# design.net
KiCad netlist of a schematic drawn in EAGLE
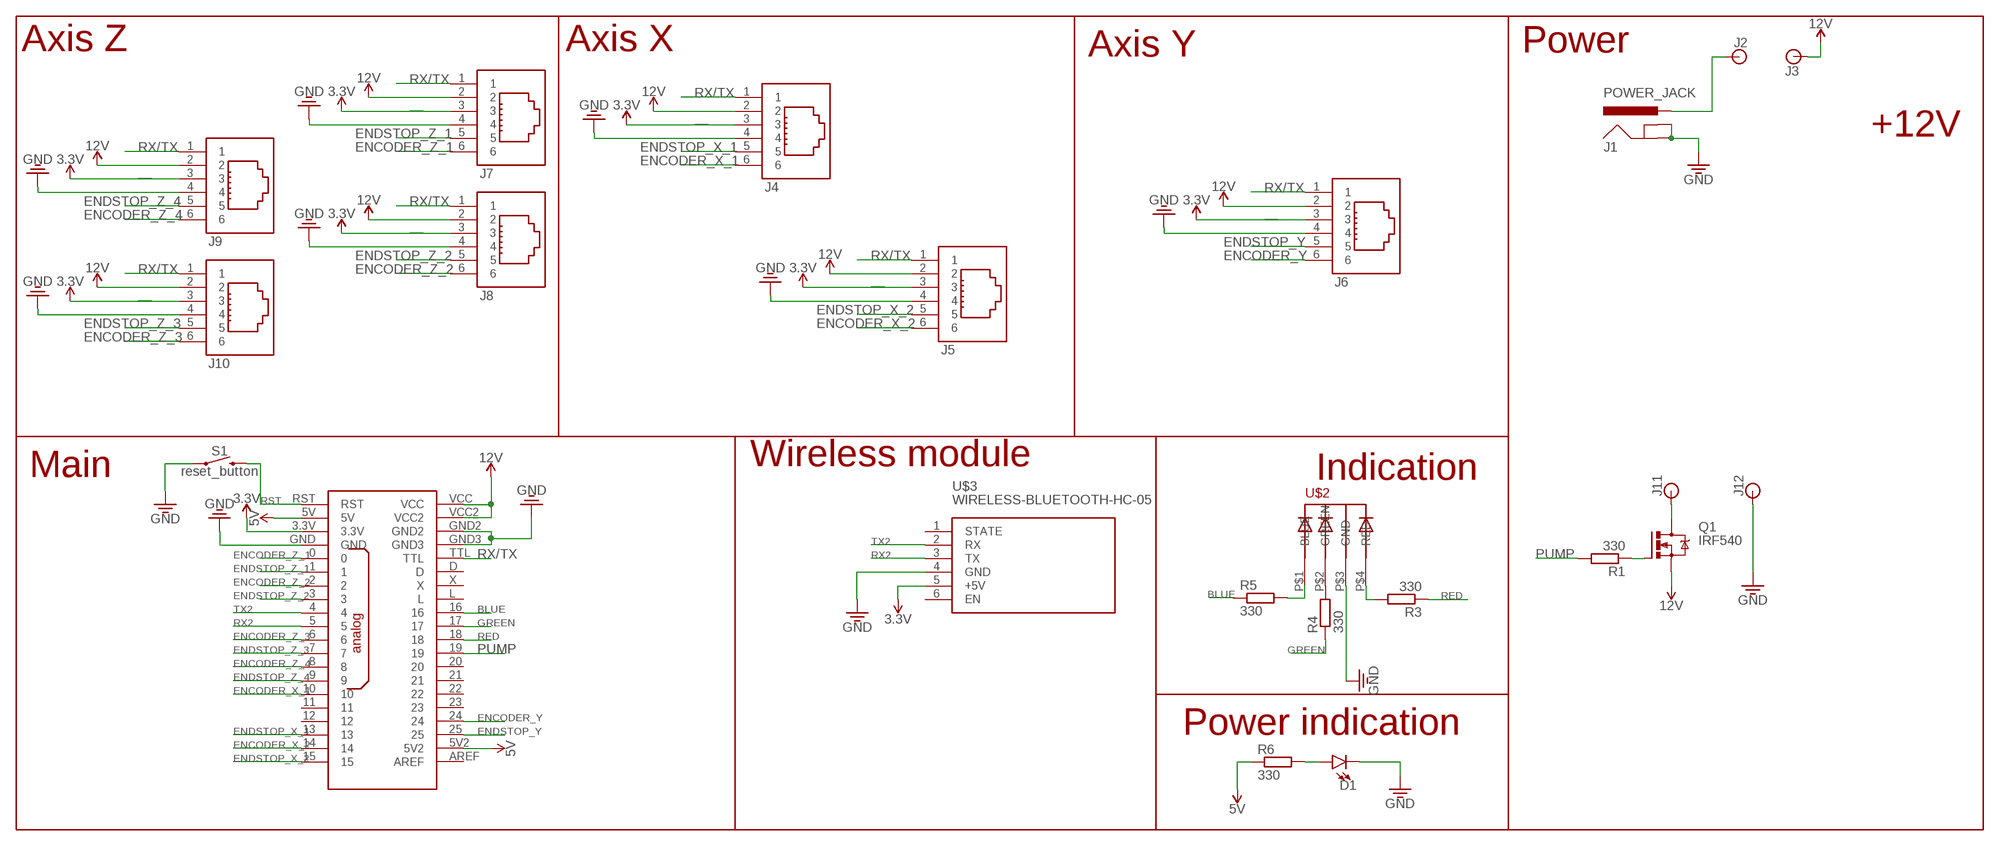
[diagram p0: schematic, sheet 1]

(export (version "E")
  (design (tool "Eeschema 10.0.6"))
  (components
    (comp (ref "D1")
      (value "LED5MM")
      (footprint "eagle-import:LED_5MM")
      (libsource (lib "eagle-import") (part "LED5MM"))
    )
    (comp (ref "J1")
      (value "POWER_JACK")
      (footprint "eagle-import:POWER_JACK_PTH")
      (libsource (lib "eagle-import") (part "POWER_JACK"))
    )
    (comp (ref "J2")
      (value "BANANA_CONN")
      (footprint "eagle-import:BANANA_CONN")
      (libsource (lib "eagle-import") (part "BANANA_CONN"))
    )
    (comp (ref "J3")
      (value "BANANA_CONN")
      (footprint "eagle-import:BANANA_CONN")
      (libsource (lib "eagle-import") (part "BANANA_CONN"))
    )
    (comp (ref "J4")
      (value "615006138421")
      (footprint "eagle-import:615006138421")
      (libsource (lib "eagle-import") (part "615006138421"))
    )
    (comp (ref "J5")
      (value "615006138421")
      (footprint "eagle-import:615006138421")
      (libsource (lib "eagle-import") (part "615006138421"))
    )
    (comp (ref "J6")
      (value "615006138421")
      (footprint "eagle-import:615006138421")
      (libsource (lib "eagle-import") (part "615006138421"))
    )
    (comp (ref "J7")
      (value "615006138421")
      (footprint "eagle-import:615006138421")
      (libsource (lib "eagle-import") (part "615006138421"))
    )
    (comp (ref "J8")
      (value "615006138421")
      (footprint "eagle-import:615006138421")
      (libsource (lib "eagle-import") (part "615006138421"))
    )
    (comp (ref "J9")
      (value "615006138421")
      (footprint "eagle-import:615006138421")
      (libsource (lib "eagle-import") (part "615006138421"))
    )
    (comp (ref "J10")
      (value "615006138421")
      (footprint "eagle-import:615006138421")
      (libsource (lib "eagle-import") (part "615006138421"))
    )
    (comp (ref "J11")
      (value "BANANA_CONN")
      (footprint "eagle-import:BANANA_CONN")
      (libsource (lib "eagle-import") (part "BANANA_CONN"))
    )
    (comp (ref "J12")
      (value "BANANA_CONN")
      (footprint "eagle-import:BANANA_CONN")
      (libsource (lib "eagle-import") (part "BANANA_CONN"))
    )
    (comp (ref "Q1")
      (value "IRF540")
      (footprint "eagle-import:TO220BV")
      (libsource (lib "eagle-import") (part "IRF540"))
    )
    (comp (ref "R1")
      (value "330")
      (footprint "eagle-import:0204_7")
      (libsource (lib "eagle-import") (part "R-EU_0204/7"))
    )
    (comp (ref "R3")
      (value "330")
      (footprint "eagle-import:0204_7")
      (libsource (lib "eagle-import") (part "R-EU_0204/7"))
    )
    (comp (ref "R4")
      (value "330")
      (footprint "eagle-import:0204_7")
      (libsource (lib "eagle-import") (part "R-EU_0204/7"))
    )
    (comp (ref "R5")
      (value "330")
      (footprint "eagle-import:0204_7")
      (libsource (lib "eagle-import") (part "R-EU_0204/7"))
    )
    (comp (ref "R6")
      (value "330")
      (footprint "eagle-import:0204_7")
      (libsource (lib "eagle-import") (part "R-EU_0204/7"))
    )
    (comp (ref "S1")
      (value "reset_button")
      (footprint "eagle-import:TACTILE_SWITCH_PTH_6.0MM")
      (libsource (lib "eagle-import") (part "MOMENTARY-SWITCH-SPST-PTH-6.0MM"))
    )
    (comp (ref "U$1")
      (value "OPENCM9.04")
      (footprint "eagle-import:OPENCM9.04")
      (libsource (lib "eagle-import") (part "OPENCM9.04"))
    )
    (comp (ref "U$2")
      (value "5MMRGBLED")
      (footprint "eagle-import:LED5MMRGB")
      (libsource (lib "eagle-import") (part "5MMRGBLED"))
    )
    (comp (ref "U$3")
      (value "WIRELESS-BLUETOOTH-HC-05")
      (footprint "eagle-import:WIRELESS-BLUETOOTH-HC-05")
      (libsource (lib "eagle-import") (part "WIRELESS-BLUETOOTH-HC-05"))
    )
  )
  (nets
    (net (code "1") (name "/BLUE") (class "Default")
      (node (ref "R5") (pin "1") (pinfunction "1_1") (pintype "passive"))
      (node (ref "U$1") (pin "16") (pinfunction "16_16") (pintype "bidirectional"))
    )
    (net (code "2") (name "/ENCODER_X_1") (class "Default")
      (node (ref "J4") (pin "6") (pinfunction "6_6") (pintype "passive"))
      (node (ref "U$1") (pin "10") (pinfunction "10_10") (pintype "bidirectional"))
    )
    (net (code "3") (name "/ENCODER_X_2") (class "Default")
      (node (ref "J5") (pin "6") (pinfunction "6_6") (pintype "passive"))
      (node (ref "U$1") (pin "14") (pinfunction "14_14") (pintype "bidirectional"))
    )
    (net (code "4") (name "/ENCODER_Y") (class "Default")
      (node (ref "J6") (pin "6") (pinfunction "6_6") (pintype "passive"))
      (node (ref "U$1") (pin "24") (pinfunction "24_24") (pintype "bidirectional"))
    )
    (net (code "5") (name "/ENCODER_Z_1") (class "Default")
      (node (ref "J7") (pin "6") (pinfunction "6_6") (pintype "passive"))
      (node (ref "U$1") (pin "0") (pinfunction "0_0") (pintype "bidirectional"))
    )
    (net (code "6") (name "/ENCODER_Z_2") (class "Default")
      (node (ref "J8") (pin "6") (pinfunction "6_6") (pintype "passive"))
      (node (ref "U$1") (pin "2") (pinfunction "2_2") (pintype "bidirectional"))
    )
    (net (code "7") (name "/ENCODER_Z_3") (class "Default")
      (node (ref "J10") (pin "6") (pinfunction "6_6") (pintype "passive"))
      (node (ref "U$1") (pin "6") (pinfunction "6_6") (pintype "bidirectional"))
    )
    (net (code "8") (name "/ENCODER_Z_4") (class "Default")
      (node (ref "J9") (pin "6") (pinfunction "6_6") (pintype "passive"))
      (node (ref "U$1") (pin "8") (pinfunction "8_8") (pintype "bidirectional"))
    )
    (net (code "9") (name "/ENDSTOP_X_1") (class "Default")
      (node (ref "J4") (pin "5") (pinfunction "5_5") (pintype "passive"))
      (node (ref "U$1") (pin "13") (pinfunction "13_13") (pintype "bidirectional"))
    )
    (net (code "10") (name "/ENDSTOP_X_2") (class "Default")
      (node (ref "J5") (pin "5") (pinfunction "5_5") (pintype "passive"))
      (node (ref "U$1") (pin "15") (pinfunction "15_15") (pintype "bidirectional"))
    )
    (net (code "11") (name "/ENDSTOP_Y") (class "Default")
      (node (ref "J6") (pin "5") (pinfunction "5_5") (pintype "passive"))
      (node (ref "U$1") (pin "25") (pinfunction "25_25") (pintype "bidirectional"))
    )
    (net (code "12") (name "/ENDSTOP_Z_1") (class "Default")
      (node (ref "J7") (pin "5") (pinfunction "5_5") (pintype "passive"))
      (node (ref "U$1") (pin "1") (pinfunction "1_1") (pintype "bidirectional"))
    )
    (net (code "13") (name "/ENDSTOP_Z_2") (class "Default")
      (node (ref "J8") (pin "5") (pinfunction "5_5") (pintype "passive"))
      (node (ref "U$1") (pin "3") (pinfunction "3_3") (pintype "bidirectional"))
    )
    (net (code "14") (name "/ENDSTOP_Z_3") (class "Default")
      (node (ref "J10") (pin "5") (pinfunction "5_5") (pintype "passive"))
      (node (ref "U$1") (pin "7") (pinfunction "7_7") (pintype "bidirectional"))
    )
    (net (code "15") (name "/ENDSTOP_Z_4") (class "Default")
      (node (ref "J9") (pin "5") (pinfunction "5_5") (pintype "passive"))
      (node (ref "U$1") (pin "9") (pinfunction "9_9") (pintype "bidirectional"))
    )
    (net (code "16") (name "/GREEN") (class "Default")
      (node (ref "R4") (pin "1") (pinfunction "1_1") (pintype "passive"))
      (node (ref "U$1") (pin "17") (pinfunction "17_17") (pintype "bidirectional"))
    )
    (net (code "17") (name "/PUMP") (class "Default")
      (node (ref "R1") (pin "2") (pinfunction "2_2") (pintype "passive"))
      (node (ref "U$1") (pin "19") (pinfunction "19_19") (pintype "bidirectional"))
    )
    (net (code "18") (name "/RED") (class "Default")
      (node (ref "R3") (pin "1") (pinfunction "1_1") (pintype "passive"))
      (node (ref "U$1") (pin "18") (pinfunction "18_18") (pintype "bidirectional"))
    )
    (net (code "19") (name "/RST") (class "Default")
      (node (ref "S1") (pin "3") (pinfunction "2_3") (pintype "passive"))
      (node (ref "U$1") (pin "RST") (pinfunction "RST_RST") (pintype "bidirectional"))
    )
    (net (code "20") (name "/RX2") (class "Default")
      (node (ref "U$1") (pin "5") (pinfunction "5_5") (pintype "bidirectional"))
      (node (ref "U$3") (pin "3") (pinfunction "TX_3") (pintype "bidirectional"))
    )
    (net (code "21") (name "/RX{slash}TX") (class "Default")
      (node (ref "J10") (pin "1") (pinfunction "1_1") (pintype "passive"))
      (node (ref "J4") (pin "1") (pinfunction "1_1") (pintype "passive"))
      (node (ref "J5") (pin "1") (pinfunction "1_1") (pintype "passive"))
      (node (ref "J6") (pin "1") (pinfunction "1_1") (pintype "passive"))
      (node (ref "J7") (pin "1") (pinfunction "1_1") (pintype "passive"))
      (node (ref "J8") (pin "1") (pinfunction "1_1") (pintype "passive"))
      (node (ref "J9") (pin "1") (pinfunction "1_1") (pintype "passive"))
      (node (ref "U$1") (pin "TTL") (pinfunction "TTL_TTL") (pintype "bidirectional"))
    )
    (net (code "22") (name "/TX2") (class "Default")
      (node (ref "U$1") (pin "4") (pinfunction "4_4") (pintype "bidirectional"))
      (node (ref "U$3") (pin "2") (pinfunction "RX_2") (pintype "bidirectional"))
    )
    (net (code "23") (name "3.3V") (class "Default")
      (node (ref "J10") (pin "3") (pinfunction "3_3") (pintype "passive"))
      (node (ref "J4") (pin "3") (pinfunction "3_3") (pintype "passive"))
      (node (ref "J5") (pin "3") (pinfunction "3_3") (pintype "passive"))
      (node (ref "J6") (pin "3") (pinfunction "3_3") (pintype "passive"))
      (node (ref "J7") (pin "3") (pinfunction "3_3") (pintype "passive"))
      (node (ref "J8") (pin "3") (pinfunction "3_3") (pintype "passive"))
      (node (ref "J9") (pin "3") (pinfunction "3_3") (pintype "passive"))
      (node (ref "U$1") (pin "3.3V") (pinfunction "3.3V_3.3V") (pintype "bidirectional"))
      (node (ref "U$3") (pin "5") (pinfunction "+5V_5") (pintype "power_in"))
    )
    (net (code "24") (name "5V") (class "Default")
      (node (ref "R6") (pin "1") (pinfunction "1_1") (pintype "passive"))
      (node (ref "U$1") (pin "5V") (pinfunction "5V_5V") (pintype "bidirectional"))
      (node (ref "U$1") (pin "5V2") (pinfunction "5V2_5V2") (pintype "bidirectional"))
    )
    (net (code "25") (name "12V") (class "Default")
      (node (ref "J10") (pin "2") (pinfunction "2_2") (pintype "passive"))
      (node (ref "J3") (pin "P$1") (pinfunction "1_P$1") (pintype "passive"))
      (node (ref "J4") (pin "2") (pinfunction "2_2") (pintype "passive"))
      (node (ref "J5") (pin "2") (pinfunction "2_2") (pintype "passive"))
      (node (ref "J6") (pin "2") (pinfunction "2_2") (pintype "passive"))
      (node (ref "J7") (pin "2") (pinfunction "2_2") (pintype "passive"))
      (node (ref "J8") (pin "2") (pinfunction "2_2") (pintype "passive"))
      (node (ref "J9") (pin "2") (pinfunction "2_2") (pintype "passive"))
      (node (ref "Q1") (pin "S") (pinfunction "S_S") (pintype "passive"))
      (node (ref "U$1") (pin "VCC") (pinfunction "VCC_VCC") (pintype "bidirectional"))
      (node (ref "U$1") (pin "VCC2") (pinfunction "VCC2_VCC2") (pintype "bidirectional"))
    )
    (net (code "26") (name "GND") (class "Default")
      (node (ref "D1") (pin "K") (pinfunction "C_K") (pintype "passive"))
      (node (ref "J1") (pin "GND") (pinfunction "GND_GND") (pintype "bidirectional"))
      (node (ref "J1") (pin "GNDBREAK") (pinfunction "GNDBREAK_GNDBREAK") (pintype "bidirectional"))
      (node (ref "J10") (pin "4") (pinfunction "4_4") (pintype "passive"))
      (node (ref "J12") (pin "P$1") (pinfunction "1_P$1") (pintype "passive"))
      (node (ref "J4") (pin "4") (pinfunction "4_4") (pintype "passive"))
      (node (ref "J5") (pin "4") (pinfunction "4_4") (pintype "passive"))
      (node (ref "J6") (pin "4") (pinfunction "4_4") (pintype "passive"))
      (node (ref "J7") (pin "4") (pinfunction "4_4") (pintype "passive"))
      (node (ref "J8") (pin "4") (pinfunction "4_4") (pintype "passive"))
      (node (ref "J9") (pin "4") (pinfunction "4_4") (pintype "passive"))
      (node (ref "S1") (pin "1") (pinfunction "1_1") (pintype "passive"))
      (node (ref "U$1") (pin "GND") (pinfunction "GND_GND") (pintype "bidirectional"))
      (node (ref "U$1") (pin "GND2") (pinfunction "GND2_GND2") (pintype "bidirectional"))
      (node (ref "U$1") (pin "GND3") (pinfunction "GND3_GND3") (pintype "bidirectional"))
      (node (ref "U$2") (pin "P$3") (pinfunction "GND_P$3") (pintype "bidirectional"))
      (node (ref "U$3") (pin "4") (pinfunction "GND_4") (pintype "power_in"))
    )
    (net (code "27") (name "Net-(D1-PadA)") (class "Default")
      (node (ref "D1") (pin "A") (pinfunction "A_A") (pintype "passive"))
      (node (ref "R6") (pin "2") (pinfunction "2_2") (pintype "passive"))
    )
    (net (code "28") (name "Net-(J2-1)") (class "Default")
      (node (ref "J1") (pin "PWR") (pinfunction "PWR_PWR") (pintype "bidirectional"))
      (node (ref "J2") (pin "P$1") (pinfunction "1_P$1") (pintype "passive"))
    )
    (net (code "29") (name "Net-(J11-1)") (class "Default")
      (node (ref "J11") (pin "P$1") (pinfunction "1_P$1") (pintype "passive"))
      (node (ref "Q1") (pin "D") (pinfunction "D_D") (pintype "passive"))
    )
    (net (code "30") (name "Net-(Q1-PadG)") (class "Default")
      (node (ref "Q1") (pin "G") (pinfunction "G_G") (pintype "passive"))
      (node (ref "R1") (pin "1") (pinfunction "1_1") (pintype "passive"))
    )
    (net (code "31") (name "Net-(U$2-BLUE)") (class "Default")
      (node (ref "R5") (pin "2") (pinfunction "2_2") (pintype "passive"))
      (node (ref "U$2") (pin "P$1") (pinfunction "BLUE_P$1") (pintype "bidirectional"))
    )
    (net (code "32") (name "Net-(U$2-GREEN)") (class "Default")
      (node (ref "R4") (pin "2") (pinfunction "2_2") (pintype "passive"))
      (node (ref "U$2") (pin "P$2") (pinfunction "GREEN_P$2") (pintype "bidirectional"))
    )
    (net (code "33") (name "Net-(U$2-RED)") (class "Default")
      (node (ref "R3") (pin "2") (pinfunction "2_2") (pintype "passive"))
      (node (ref "U$2") (pin "P$4") (pinfunction "RED_P$4") (pintype "bidirectional"))
    )
    (net (code "34") (name "unconnected-(U$1-Pad11)") (class "Default")
      (node (ref "U$1") (pin "11") (pinfunction "11_11") (pintype "bidirectional"))
    )
    (net (code "35") (name "unconnected-(U$1-Pad12)") (class "Default")
      (node (ref "U$1") (pin "12") (pinfunction "12_12") (pintype "bidirectional"))
    )
    (net (code "36") (name "unconnected-(U$1-Pad20)") (class "Default")
      (node (ref "U$1") (pin "20") (pinfunction "20_20") (pintype "bidirectional"))
    )
    (net (code "37") (name "unconnected-(U$1-Pad21)") (class "Default")
      (node (ref "U$1") (pin "21") (pinfunction "21_21") (pintype "bidirectional"))
    )
    (net (code "38") (name "unconnected-(U$1-Pad22)") (class "Default")
      (node (ref "U$1") (pin "22") (pinfunction "22_22") (pintype "bidirectional"))
    )
    (net (code "39") (name "unconnected-(U$1-Pad23)") (class "Default")
      (node (ref "U$1") (pin "23") (pinfunction "23_23") (pintype "bidirectional"))
    )
    (net (code "40") (name "unconnected-(U$1-PadAREF)") (class "Default")
      (node (ref "U$1") (pin "AREF") (pinfunction "AREF_AREF") (pintype "bidirectional"))
    )
    (net (code "41") (name "unconnected-(U$1-PadD)") (class "Default")
      (node (ref "U$1") (pin "D") (pinfunction "D_D") (pintype "bidirectional"))
    )
    (net (code "42") (name "unconnected-(U$1-PadL)") (class "Default")
      (node (ref "U$1") (pin "L") (pinfunction "L_L") (pintype "bidirectional"))
    )
    (net (code "43") (name "unconnected-(U$1-PadX)") (class "Default")
      (node (ref "U$1") (pin "X") (pinfunction "X_X") (pintype "bidirectional"))
    )
    (net (code "44") (name "unconnected-(U$3-EN-Pad6)") (class "Default")
      (node (ref "U$3") (pin "6") (pinfunction "EN_6") (pintype "bidirectional"))
    )
    (net (code "45") (name "unconnected-(U$3-STATE-Pad1)") (class "Default")
      (node (ref "U$3") (pin "1") (pinfunction "STATE_1") (pintype "bidirectional"))
    )
  )
)
